# moo-moo-FOC.net
KiCad netlist of a schematic drawn in Altium Designer
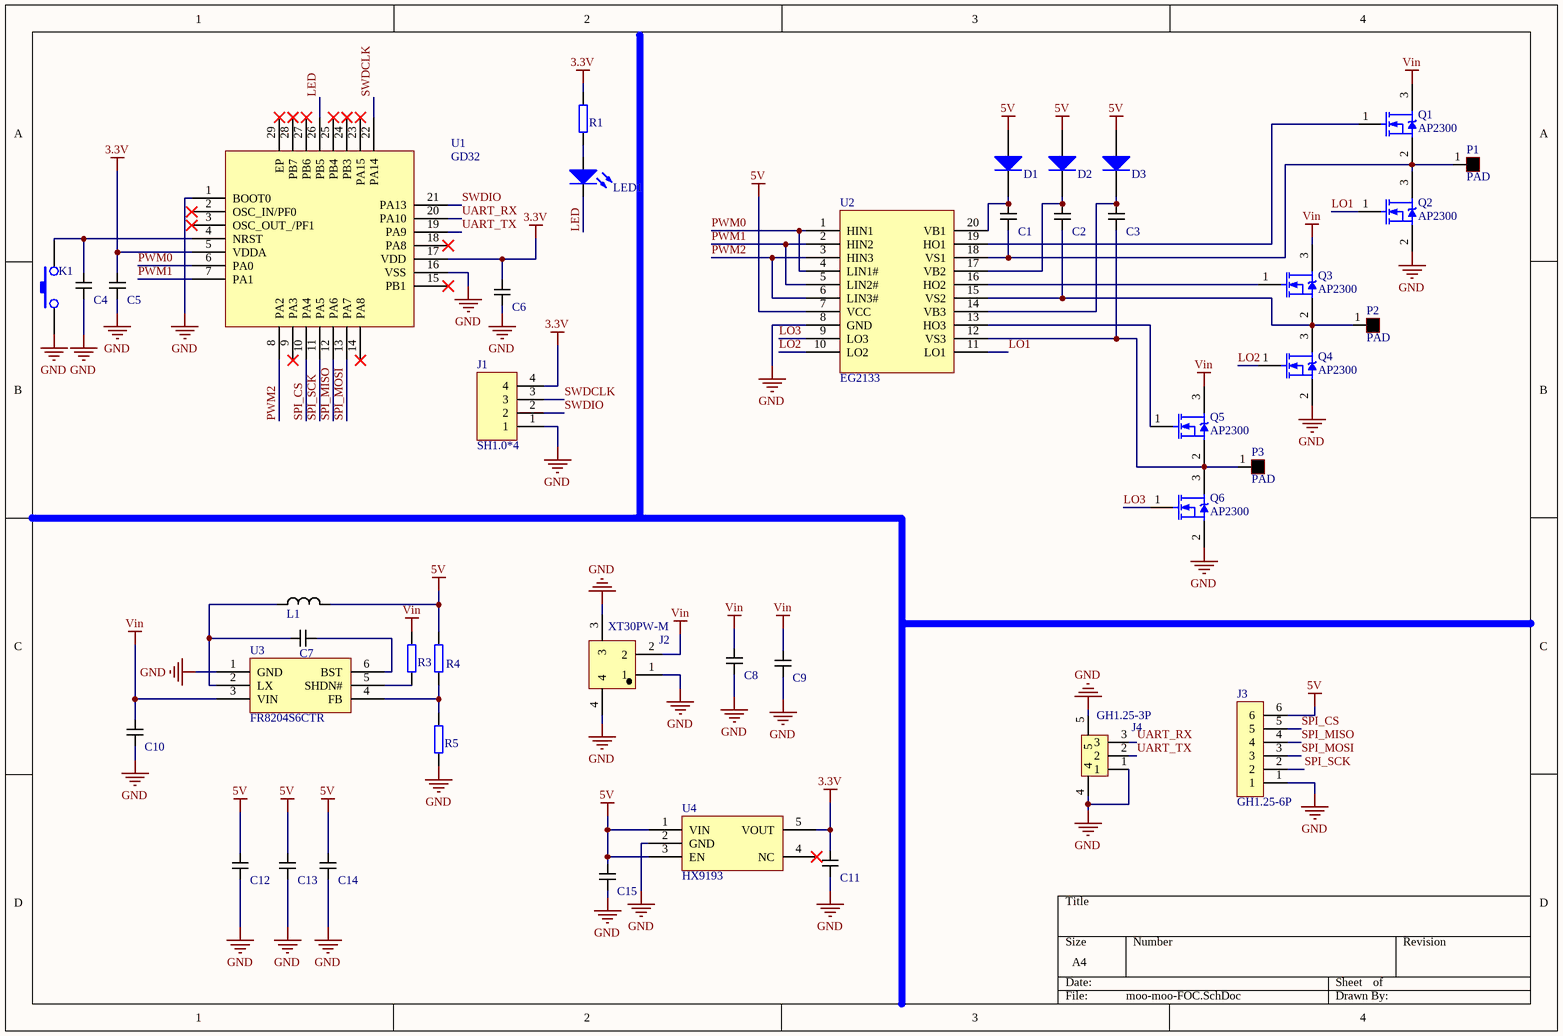
[diagram p0: moo-moo-FOC.SchDoc]

(export (version "E")
  (design (tool "Eeschema 10.0.6"))
  (components
    (comp (ref "C1")
      (value "100nF")
      (footprint "0603-CAP")
      (description "无极性贴片电容")
      (libsource (lib "moo-moo-FOC") (part "电容"))
    )
    (comp (ref "C2")
      (value "100nF")
      (footprint "0603-CAP")
      (description "无极性贴片电容")
      (libsource (lib "moo-moo-FOC") (part "电容"))
    )
    (comp (ref "C3")
      (value "100nF")
      (footprint "0603-CAP")
      (description "无极性贴片电容")
      (libsource (lib "moo-moo-FOC") (part "电容"))
    )
    (comp (ref "C4")
      (value "100nF")
      (footprint "0603-CAP")
      (description "无极性贴片电容")
      (libsource (lib "moo-moo-FOC") (part "电容"))
    )
    (comp (ref "C5")
      (value "100nF")
      (footprint "0603-CAP")
      (description "无极性贴片电容")
      (libsource (lib "moo-moo-FOC") (part "电容"))
    )
    (comp (ref "C6")
      (value "100nF")
      (footprint "0603-CAP")
      (description "无极性贴片电容")
      (libsource (lib "moo-moo-FOC") (part "电容"))
    )
    (comp (ref "C7")
      (value "100nF")
      (footprint "0603-CAP")
      (description "无极性贴片电容")
      (libsource (lib "moo-moo-FOC") (part "电容"))
    )
    (comp (ref "C8")
      (value "10uF")
      (footprint "0603-CAP")
      (description "无极性贴片电容")
      (libsource (lib "moo-moo-FOC") (part "电容"))
    )
    (comp (ref "C9")
      (value "10uF")
      (footprint "0603-CAP")
      (description "无极性贴片电容")
      (libsource (lib "moo-moo-FOC") (part "电容"))
    )
    (comp (ref "C10")
      (value "10uF")
      (footprint "0603-CAP")
      (description "无极性贴片电容")
      (libsource (lib "moo-moo-FOC") (part "电容"))
    )
    (comp (ref "C11")
      (value "100nF")
      (footprint "0603-CAP")
      (description "无极性贴片电容")
      (libsource (lib "moo-moo-FOC") (part "电容"))
    )
    (comp (ref "C12")
      (value "10uF")
      (footprint "0603-CAP")
      (description "无极性贴片电容")
      (libsource (lib "moo-moo-FOC") (part "电容"))
    )
    (comp (ref "C13")
      (value "10uF")
      (footprint "0603-CAP")
      (description "无极性贴片电容")
      (libsource (lib "moo-moo-FOC") (part "电容"))
    )
    (comp (ref "C14")
      (value "10uF")
      (footprint "0603-CAP")
      (description "无极性贴片电容")
      (libsource (lib "moo-moo-FOC") (part "电容"))
    )
    (comp (ref "C15")
      (value "100nF")
      (footprint "0603-CAP")
      (description "无极性贴片电容")
      (libsource (lib "moo-moo-FOC") (part "电容"))
    )
    (comp (ref "D1")
      (value "二极管")
      (footprint "二极管")
      (description "通用二极管")
      (libsource (lib "moo-moo-FOC") (part "二极管"))
    )
    (comp (ref "D2")
      (value "二极管")
      (footprint "二极管")
      (description "通用二极管")
      (libsource (lib "moo-moo-FOC") (part "二极管"))
    )
    (comp (ref "D3")
      (value "二极管")
      (footprint "二极管")
      (description "通用二极管")
      (libsource (lib "moo-moo-FOC") (part "二极管"))
    )
    (comp (ref "J1")
      (value "SH1.0*4")
      (footprint "SH1.0-WT-4P")
      (libsource (lib "moo-moo-FOC") (part "SH1.0*4"))
    )
    (comp (ref "J2")
      (value "XT30PW-M")
      (footprint "XT30PW-M公头")
      (libsource (lib "moo-moo-FOC") (part "XT30PW-M公头"))
    )
    (comp (ref "J3")
      (value "GH1.25-6P")
      (footprint "GH1.25-WT-6P")
      (libsource (lib "moo-moo-FOC") (part "GH1.25-6P"))
    )
    (comp (ref "J4")
      (value "GH1.25-3P")
      (footprint "GH1.25-WT-3P")
      (libsource (lib "moo-moo-FOC") (part "GH1.25-3P"))
    )
    (comp (ref "K1")
      (value "key")
      (footprint "轻触开关")
      (description "按键")
      (libsource (lib "moo-moo-FOC") (part "轻触开关"))
    )
    (comp (ref "L1")
      (value "4.7uH")
      (footprint "功率电感")
      (description "普通电感")
      (fields (field (name "PUBLISHER") "Altium Limited"))
      (libsource (lib "moo-moo-FOC") (part "电感"))
    )
    (comp (ref "LED1") (value "发光二极管") (footprint "0603-LED") (libsource (lib "moo-moo-FOC") (part "发光二极管")))
    (comp (ref "P1") (value "PAD") (footprint "PAD") (libsource (lib "moo-moo-FOC") (part "PAD")))
    (comp (ref "P2") (value "PAD") (footprint "PAD") (libsource (lib "moo-moo-FOC") (part "PAD")))
    (comp (ref "P3") (value "PAD") (footprint "PAD") (libsource (lib "moo-moo-FOC") (part "PAD")))
    (comp (ref "Q1") (value "AP2300") (footprint "AP2300") (libsource (lib "moo-moo-FOC") (part "AP2300")))
    (comp (ref "Q2") (value "AP2300") (footprint "AP2300") (libsource (lib "moo-moo-FOC") (part "AP2300")))
    (comp (ref "Q3") (value "AP2300") (footprint "AP2300") (libsource (lib "moo-moo-FOC") (part "AP2300")))
    (comp (ref "Q4") (value "AP2300") (footprint "AP2300") (libsource (lib "moo-moo-FOC") (part "AP2300")))
    (comp (ref "Q5") (value "AP2300") (footprint "AP2300") (libsource (lib "moo-moo-FOC") (part "AP2300")))
    (comp (ref "Q6") (value "AP2300") (footprint "AP2300") (libsource (lib "moo-moo-FOC") (part "AP2300")))
    (comp (ref "R1")
      (value "10k")
      (footprint "0603-RES")
      (description "电阻")
      (libsource (lib "moo-moo-FOC") (part "电阻"))
    )
    (comp (ref "R3")
      (value "100K")
      (footprint "0603-RES")
      (description "电阻")
      (libsource (lib "moo-moo-FOC") (part "电阻"))
    )
    (comp (ref "R4")
      (value "30.9K")
      (footprint "0603-RES")
      (description "电阻")
      (libsource (lib "moo-moo-FOC") (part "电阻"))
    )
    (comp (ref "R5")
      (value "5.76K")
      (footprint "0603-RES")
      (description "电阻")
      (libsource (lib "moo-moo-FOC") (part "电阻"))
    )
    (comp (ref "U1")
      (value "GD32")
      (footprint "QFN-28-0.4")
      (libsource (lib "moo-moo-FOC") (part "GD32F130G6U6TR"))
    )
    (comp (ref "U2") (value "EG2133") (footprint "EG2133") (libsource (lib "moo-moo-FOC") (part "EG2133")))
    (comp (ref "U3")
      (value "FR8204S6CTR")
      (footprint "FR8204")
      (libsource (lib "moo-moo-FOC") (part "FR8204S6CTR"))
    )
    (comp (ref "U4")
      (value "HX9193")
      (footprint "HX9193")
      (libsource (lib "moo-moo-FOC") (part "HX9193-33GB"))
    )
  )
  (nets
    (net (code "1") (name "/LED") (class "Default")
      (node (ref "LED1") (pin "2") (pinfunction "2_2") (pintype "passive"))
      (node (ref "U1") (pin "26") (pinfunction "PB5_26") (pintype "passive"))
    )
    (net (code "2") (name "/LO1") (class "Default")
      (node (ref "Q2") (pin "1") (pinfunction "G_1") (pintype "passive"))
      (node (ref "U2") (pin "11") (pinfunction "LO1_11") (pintype "passive"))
    )
    (net (code "3") (name "/LO2") (class "Default")
      (node (ref "Q4") (pin "1") (pinfunction "G_1") (pintype "passive"))
      (node (ref "U2") (pin "10") (pinfunction "LO2_10") (pintype "passive"))
    )
    (net (code "4") (name "/LO3") (class "Default")
      (node (ref "Q6") (pin "1") (pinfunction "G_1") (pintype "passive"))
      (node (ref "U2") (pin "9") (pinfunction "LO3_9") (pintype "passive"))
    )
    (net (code "5") (name "/PWM0") (class "Default")
      (node (ref "U1") (pin "6") (pinfunction "PA0_6") (pintype "passive"))
      (node (ref "U2") (pin "1") (pinfunction "HIN1_1") (pintype "passive"))
      (node (ref "U2") (pin "4") (pinfunction "LIN1#_4") (pintype "passive"))
    )
    (net (code "6") (name "/PWM1") (class "Default")
      (node (ref "U1") (pin "7") (pinfunction "PA1_7") (pintype "passive"))
      (node (ref "U2") (pin "2") (pinfunction "HIN2_2") (pintype "passive"))
      (node (ref "U2") (pin "5") (pinfunction "LIN2#_5") (pintype "passive"))
    )
    (net (code "7") (name "/PWM2") (class "Default")
      (node (ref "U1") (pin "8") (pinfunction "PA2_8") (pintype "passive"))
      (node (ref "U2") (pin "3") (pinfunction "HIN3_3") (pintype "passive"))
      (node (ref "U2") (pin "6") (pinfunction "LIN3#_6") (pintype "passive"))
    )
    (net (code "8") (name "/SPI_CS") (class "Default")
      (node (ref "J3") (pin "5") (pinfunction "5_5") (pintype "passive"))
      (node (ref "U1") (pin "10") (pinfunction "PA4_10") (pintype "passive"))
    )
    (net (code "9") (name "/SPI_MISO") (class "Default")
      (node (ref "J3") (pin "4") (pinfunction "4_4") (pintype "passive"))
      (node (ref "U1") (pin "12") (pinfunction "PA6_12") (pintype "passive"))
    )
    (net (code "10") (name "/SPI_MOSI") (class "Default")
      (node (ref "J3") (pin "3") (pinfunction "3_3") (pintype "passive"))
      (node (ref "U1") (pin "13") (pinfunction "PA7_13") (pintype "passive"))
    )
    (net (code "11") (name "/SPI_SCK") (class "Default")
      (node (ref "J3") (pin "2") (pinfunction "2_2") (pintype "passive"))
      (node (ref "U1") (pin "11") (pinfunction "PA5_11") (pintype "passive"))
    )
    (net (code "12") (name "/SWDCLK") (class "Default")
      (node (ref "J1") (pin "3") (pinfunction "3_3") (pintype "passive"))
      (node (ref "U1") (pin "22") (pinfunction "PA14_22") (pintype "passive"))
    )
    (net (code "13") (name "/SWDIO") (class "Default")
      (node (ref "J1") (pin "2") (pinfunction "2_2") (pintype "passive"))
      (node (ref "U1") (pin "21") (pinfunction "PA13_21") (pintype "passive"))
    )
    (net (code "14") (name "/UART_RX") (class "Default")
      (node (ref "J4") (pin "3") (pinfunction "3_3") (pintype "passive"))
      (node (ref "U1") (pin "20") (pinfunction "PA10_20") (pintype "passive"))
    )
    (net (code "15") (name "/UART_TX") (class "Default")
      (node (ref "J4") (pin "2") (pinfunction "2_2") (pintype "passive"))
      (node (ref "U1") (pin "19") (pinfunction "PA9_19") (pintype "passive"))
    )
    (net (code "16") (name "3.3V") (class "Default")
      (node (ref "C11") (pin "1") (pintype "passive"))
      (node (ref "C5") (pin "1") (pintype "passive"))
      (node (ref "C6") (pin "1") (pintype "passive"))
      (node (ref "J1") (pin "4") (pinfunction "4_4") (pintype "passive"))
      (node (ref "R1") (pin "1") (pinfunction "1_1") (pintype "passive"))
      (node (ref "U1") (pin "17") (pinfunction "VDD_17") (pintype "passive"))
      (node (ref "U1") (pin "5") (pinfunction "VDDA_5") (pintype "passive"))
      (node (ref "U4") (pin "5") (pinfunction "VOUT_5") (pintype "passive"))
    )
    (net (code "17") (name "5V") (class "Default")
      (node (ref "C12") (pin "1") (pintype "passive"))
      (node (ref "C13") (pin "1") (pintype "passive"))
      (node (ref "C14") (pin "1") (pintype "passive"))
      (node (ref "C15") (pin "1") (pintype "passive"))
      (node (ref "D1") (pin "1") (pinfunction "A_1") (pintype "passive"))
      (node (ref "D2") (pin "1") (pinfunction "A_1") (pintype "passive"))
      (node (ref "D3") (pin "1") (pinfunction "A_1") (pintype "passive"))
      (node (ref "J3") (pin "6") (pinfunction "6_6") (pintype "passive"))
      (node (ref "L1") (pin "2") (pinfunction "2_2") (pintype "passive"))
      (node (ref "R4") (pin "1") (pinfunction "1_1") (pintype "passive"))
      (node (ref "U2") (pin "7") (pinfunction "VCC_7") (pintype "passive"))
      (node (ref "U4") (pin "1") (pinfunction "VIN_1") (pintype "passive"))
      (node (ref "U4") (pin "3") (pinfunction "EN_3") (pintype "passive"))
    )
    (net (code "18") (name "GND") (class "Default")
      (node (ref "C10") (pin "2") (pintype "passive"))
      (node (ref "C11") (pin "2") (pintype "passive"))
      (node (ref "C12") (pin "2") (pintype "passive"))
      (node (ref "C13") (pin "2") (pintype "passive"))
      (node (ref "C14") (pin "2") (pintype "passive"))
      (node (ref "C15") (pin "2") (pintype "passive"))
      (node (ref "C4") (pin "2") (pintype "passive"))
      (node (ref "C5") (pin "2") (pintype "passive"))
      (node (ref "C6") (pin "2") (pintype "passive"))
      (node (ref "C8") (pin "2") (pintype "passive"))
      (node (ref "C9") (pin "2") (pintype "passive"))
      (node (ref "J1") (pin "1") (pinfunction "1_1") (pintype "passive"))
      (node (ref "J2") (pin "1") (pinfunction "1_1") (pintype "passive"))
      (node (ref "J2") (pin "3") (pinfunction "3_3") (pintype "passive"))
      (node (ref "J2") (pin "4") (pinfunction "4_4") (pintype "passive"))
      (node (ref "J3") (pin "1") (pinfunction "1_1") (pintype "passive"))
      (node (ref "J4") (pin "1") (pinfunction "1_1") (pintype "passive"))
      (node (ref "J4") (pin "4") (pinfunction "4_4") (pintype "passive"))
      (node (ref "J4") (pin "5") (pinfunction "5_5") (pintype "passive"))
      (node (ref "K1") (pin "1") (pinfunction "1_1") (pintype "passive"))
      (node (ref "Q2") (pin "2") (pinfunction "S_2") (pintype "passive"))
      (node (ref "Q4") (pin "2") (pinfunction "S_2") (pintype "passive"))
      (node (ref "Q6") (pin "2") (pinfunction "S_2") (pintype "passive"))
      (node (ref "R5") (pin "2") (pinfunction "2_2") (pintype "passive"))
      (node (ref "U1") (pin "1") (pinfunction "BOOT0_1") (pintype "passive"))
      (node (ref "U1") (pin "16") (pinfunction "VSS_16") (pintype "passive"))
      (node (ref "U2") (pin "8") (pinfunction "GND_8") (pintype "passive"))
      (node (ref "U3") (pin "1") (pinfunction "GND_1") (pintype "passive"))
      (node (ref "U4") (pin "2") (pinfunction "GND_2") (pintype "passive"))
    )
    (net (code "19") (name "Net-(D1-K)") (class "Default")
      (node (ref "C1") (pin "1") (pintype "passive"))
      (node (ref "D1") (pin "2") (pinfunction "K_2") (pintype "passive"))
      (node (ref "U2") (pin "20") (pinfunction "VB1_20") (pintype "passive"))
    )
    (net (code "20") (name "Net-(D2-K)") (class "Default")
      (node (ref "C2") (pin "1") (pintype "passive"))
      (node (ref "D2") (pin "2") (pinfunction "K_2") (pintype "passive"))
      (node (ref "U2") (pin "17") (pinfunction "VB2_17") (pintype "passive"))
    )
    (net (code "21") (name "Net-(D3-K)") (class "Default")
      (node (ref "C3") (pin "1") (pintype "passive"))
      (node (ref "D3") (pin "2") (pinfunction "K_2") (pintype "passive"))
      (node (ref "U2") (pin "14") (pinfunction "VB3_14") (pintype "passive"))
    )
    (net (code "22") (name "Net-(LED1-Pad1)") (class "Default")
      (node (ref "LED1") (pin "1") (pinfunction "1_1") (pintype "passive"))
      (node (ref "R1") (pin "2") (pinfunction "2_2") (pintype "passive"))
    )
    (net (code "23") (name "Net-(Q1-G)") (class "Default")
      (node (ref "Q1") (pin "1") (pinfunction "G_1") (pintype "passive"))
      (node (ref "U2") (pin "19") (pinfunction "HO1_19") (pintype "passive"))
    )
    (net (code "24") (name "Net-(Q1-S)") (class "Default")
      (node (ref "C1") (pin "2") (pintype "passive"))
      (node (ref "P1") (pin "1") (pinfunction "1_1") (pintype "passive"))
      (node (ref "Q1") (pin "2") (pinfunction "S_2") (pintype "passive"))
      (node (ref "Q2") (pin "3") (pinfunction "3_3") (pintype "passive"))
      (node (ref "U2") (pin "18") (pinfunction "VS1_18") (pintype "passive"))
    )
    (net (code "25") (name "Net-(Q3-G)") (class "Default")
      (node (ref "Q3") (pin "1") (pinfunction "G_1") (pintype "passive"))
      (node (ref "U2") (pin "16") (pinfunction "HO2_16") (pintype "passive"))
    )
    (net (code "26") (name "Net-(Q3-S)") (class "Default")
      (node (ref "C2") (pin "2") (pintype "passive"))
      (node (ref "P2") (pin "1") (pinfunction "1_1") (pintype "passive"))
      (node (ref "Q3") (pin "2") (pinfunction "S_2") (pintype "passive"))
      (node (ref "Q4") (pin "3") (pinfunction "3_3") (pintype "passive"))
      (node (ref "U2") (pin "15") (pinfunction "VS2_15") (pintype "passive"))
    )
    (net (code "27") (name "Net-(Q5-G)") (class "Default")
      (node (ref "Q5") (pin "1") (pinfunction "G_1") (pintype "passive"))
      (node (ref "U2") (pin "13") (pinfunction "HO3_13") (pintype "passive"))
    )
    (net (code "28") (name "Net-(Q5-S)") (class "Default")
      (node (ref "C3") (pin "2") (pintype "passive"))
      (node (ref "P3") (pin "1") (pinfunction "1_1") (pintype "passive"))
      (node (ref "Q5") (pin "2") (pinfunction "S_2") (pintype "passive"))
      (node (ref "Q6") (pin "3") (pinfunction "3_3") (pintype "passive"))
      (node (ref "U2") (pin "12") (pinfunction "VS3_12") (pintype "passive"))
    )
    (net (code "29") (name "Net-(U1-NRST)") (class "Default")
      (node (ref "C4") (pin "1") (pintype "passive"))
      (node (ref "K1") (pin "2") (pinfunction "2_2") (pintype "passive"))
      (node (ref "U1") (pin "4") (pinfunction "NRST_4") (pintype "passive"))
    )
    (net (code "30") (name "Net-(U3-BST)") (class "Default")
      (node (ref "C7") (pin "2") (pintype "passive"))
      (node (ref "U3") (pin "6") (pinfunction "BST_6") (pintype "passive"))
    )
    (net (code "31") (name "Net-(U3-FB)") (class "Default")
      (node (ref "R4") (pin "2") (pinfunction "2_2") (pintype "passive"))
      (node (ref "R5") (pin "1") (pinfunction "1_1") (pintype "passive"))
      (node (ref "U3") (pin "4") (pinfunction "FB_4") (pintype "passive"))
    )
    (net (code "32") (name "Net-(U3-LX)") (class "Default")
      (node (ref "C7") (pin "1") (pintype "passive"))
      (node (ref "L1") (pin "1") (pinfunction "1_1") (pintype "passive"))
      (node (ref "U3") (pin "2") (pinfunction "LX_2") (pintype "passive"))
    )
    (net (code "33") (name "Net-(U3-SHDN#)") (class "Default")
      (node (ref "R3") (pin "2") (pinfunction "2_2") (pintype "passive"))
      (node (ref "U3") (pin "5") (pinfunction "SHDN#_5") (pintype "passive"))
    )
    (net (code "34") (name "Vin") (class "Default")
      (node (ref "C10") (pin "1") (pintype "passive"))
      (node (ref "C8") (pin "1") (pintype "passive"))
      (node (ref "C9") (pin "1") (pintype "passive"))
      (node (ref "J2") (pin "2") (pinfunction "2_2") (pintype "passive"))
      (node (ref "Q1") (pin "3") (pinfunction "3_3") (pintype "passive"))
      (node (ref "Q3") (pin "3") (pinfunction "3_3") (pintype "passive"))
      (node (ref "Q5") (pin "3") (pinfunction "3_3") (pintype "passive"))
      (node (ref "R3") (pin "1") (pinfunction "1_1") (pintype "passive"))
      (node (ref "U3") (pin "3") (pinfunction "VIN_3") (pintype "passive"))
    )
    (net (code "35") (name "unconnected-(U1-EP-Pad29)") (class "Default")
      (node (ref "U1") (pin "29") (pinfunction "EP_29") (pintype "passive+no_connect"))
    )
    (net (code "36") (name "unconnected-(U1-OSC_IN{slash}PF0-Pad2)") (class "Default")
      (node (ref "U1") (pin "2") (pinfunction "OSC_IN/PF0_2") (pintype "passive+no_connect"))
    )
    (net (code "37") (name "unconnected-(U1-OSC_OUT_{slash}PF1-Pad3)") (class "Default")
      (node (ref "U1") (pin "3") (pinfunction "OSC_OUT_/PF1_3") (pintype "passive+no_connect"))
    )
    (net (code "38") (name "unconnected-(U1-PA3-Pad9)") (class "Default")
      (node (ref "U1") (pin "9") (pinfunction "PA3_9") (pintype "passive+no_connect"))
    )
    (net (code "39") (name "unconnected-(U1-PA8-Pad14)") (class "Default")
      (node (ref "U1") (pin "14") (pinfunction "PA8_14") (pintype "passive+no_connect"))
    )
    (net (code "40") (name "unconnected-(U1-PA8-Pad18)") (class "Default")
      (node (ref "U1") (pin "18") (pinfunction "PA8_18") (pintype "passive+no_connect"))
    )
    (net (code "41") (name "unconnected-(U1-PA15-Pad23)") (class "Default")
      (node (ref "U1") (pin "23") (pinfunction "PA15_23") (pintype "passive+no_connect"))
    )
    (net (code "42") (name "unconnected-(U1-PB1-Pad15)") (class "Default")
      (node (ref "U1") (pin "15") (pinfunction "PB1_15") (pintype "passive+no_connect"))
    )
    (net (code "43") (name "unconnected-(U1-PB3-Pad24)") (class "Default")
      (node (ref "U1") (pin "24") (pinfunction "PB3_24") (pintype "passive+no_connect"))
    )
    (net (code "44") (name "unconnected-(U1-PB4-Pad25)") (class "Default")
      (node (ref "U1") (pin "25") (pinfunction "PB4_25") (pintype "passive+no_connect"))
    )
    (net (code "45") (name "unconnected-(U1-PB6-Pad27)") (class "Default")
      (node (ref "U1") (pin "27") (pinfunction "PB6_27") (pintype "passive+no_connect"))
    )
    (net (code "46") (name "unconnected-(U1-PB7-Pad28)") (class "Default")
      (node (ref "U1") (pin "28") (pinfunction "PB7_28") (pintype "passive+no_connect"))
    )
    (net (code "47") (name "unconnected-(U4-NC-Pad4)") (class "Default")
      (node (ref "U4") (pin "4") (pinfunction "NC_4") (pintype "passive+no_connect"))
    )
  )
)
